# PCB_board.net
KiCad netlist of a schematic drawn in EAGLE
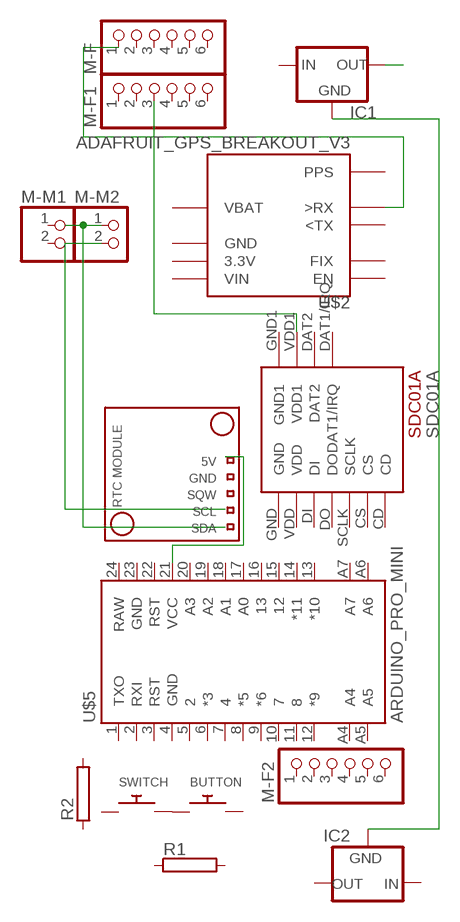
[diagram p0: schematic, sheet 1]

(export (version "E")
  (design (tool "Eeschema 10.0.6"))
  (components
    (comp (ref "BUTTON")
      (value "SWITCH_PUSHBUTTONSOFTTOUCHSMD_SJ")
      (footprint "eagle-import:PUSHBUTTON_SMD_SJ")
      (libsource (lib "eagle-import") (part "SWITCH_PUSHBUTTONSOFTTOUCHSMD_SJ"))
    )
    (comp (ref "IC1")
      (value "78XX/TO3")
      (footprint "eagle-import:TO3_78")
      (libsource (lib "eagle-import") (part "78XX/TO3"))
    )
    (comp (ref "IC2")
      (value "78XX/TO3")
      (footprint "eagle-import:TO3_78")
      (libsource (lib "eagle-import") (part "78XX/TO3"))
    )
    (comp (ref "M-F")
      (value "PINHD-1X6")
      (footprint "eagle-import:1X06")
      (libsource (lib "eagle-import") (part "PINHD-1X6"))
    )
    (comp (ref "M-F1")
      (value "PINHD-1X6")
      (footprint "eagle-import:1X06")
      (libsource (lib "eagle-import") (part "PINHD-1X6"))
    )
    (comp (ref "M-F2")
      (value "PINHD-1X6")
      (footprint "eagle-import:1X06")
      (libsource (lib "eagle-import") (part "PINHD-1X6"))
    )
    (comp (ref "M-M1")
      (value "PINHD-1X2")
      (footprint "eagle-import:1X02")
      (libsource (lib "eagle-import") (part "PINHD-1X2"))
    )
    (comp (ref "M-M2")
      (value "PINHD-1X2")
      (footprint "eagle-import:1X02")
      (libsource (lib "eagle-import") (part "PINHD-1X2"))
    )
    (comp (ref "R1")
      (value "RMG100-V")
      (footprint "eagle-import:TO-247-2V")
      (libsource (lib "eagle-import") (part "RMG100-V"))
    )
    (comp (ref "R2")
      (value "RMG100-V")
      (footprint "eagle-import:TO-247-2V")
      (libsource (lib "eagle-import") (part "RMG100-V"))
    )
    (comp (ref "SWITCH")
      (value "SWITCH_PUSHBUTTONEVQ-PE")
      (footprint "eagle-import:TACT_PANA-EVQ")
      (libsource (lib "eagle-import") (part "SWITCH_PUSHBUTTONEVQ-PE"))
    )
    (comp (ref "U$1")
      (value "REAL_TIME_CLOCK")
      (footprint "eagle-import:REAL_TIME_CLOCK")
      (libsource (lib "eagle-import") (part "REAL_TIME_CLOCK"))
    )
    (comp (ref "U$2")
      (value "ADAFRUIT_GPS_BREAKOUT_V3")
      (footprint "eagle-import:ADAFRUIT_GPS_BREAKOUT_V3")
      (libsource (lib "eagle-import") (part "ADAFRUIT_GPS_BREAKOUT_V3"))
    )
    (comp (ref "U$3")
      (value "SDC01A")
      (footprint "eagle-import:SDC01A")
      (libsource (lib "eagle-import") (part "SDC01A"))
    )
    (comp (ref "U$5")
      (value "ARDUINO_PRO_MINI")
      (footprint "eagle-import:ARDUINO_PRO_MINI")
      (libsource (lib "eagle-import") (part "ARDUINO_PRO_MINI"))
    )
  )
  (nets
    (net (code "1") (name "/3.3V") (class "Default")
      (node (ref "U$2") (pin "3.3V") (pinfunction "3.3V_3.3V") (pintype "power_in"))
    )
    (net (code "2") (name "/GND") (class "Default")
      (node (ref "U$2") (pin "GND") (pinfunction "GND_GND") (pintype "power_in"))
    )
    (net (code "3") (name "/VBAT") (class "Default")
      (node (ref "U$2") (pin "VBAT") (pinfunction "VBAT_VBAT") (pintype "power_in"))
    )
    (net (code "4") (name "/VIN") (class "Default")
      (node (ref "U$2") (pin "VIN") (pinfunction "VIN_VIN") (pintype "power_in"))
    )
    (net (code "5") (name "Net-(BUTTON-PadP$1)") (class "Default")
      (node (ref "BUTTON") (pin "P$1") (pinfunction "P$1_P$1") (pintype "passive"))
      (node (ref "SWITCH") (pin "P$2") (pinfunction "P$2_P$2") (pintype "passive"))
    )
    (net (code "6") (name "Net-(IC1-GND)") (class "Default")
      (node (ref "IC1") (pin "3") (pinfunction "GND_3") (pintype "input"))
      (node (ref "IC2") (pin "3") (pinfunction "GND_3") (pintype "input"))
    )
    (net (code "7") (name "Net-(M-F1-Pad3)") (class "Default")
      (node (ref "M-F1") (pin "3") (pinfunction "3_3") (pintype "passive"))
      (node (ref "U$3") (pin "VDD1") (pinfunction "VDD1_VDD1") (pintype "bidirectional"))
    )
    (net (code "8") (name "Net-(U$2->RX)") (class "Default")
      (node (ref "M-F") (pin "1") (pinfunction "1_1") (pintype "passive"))
      (node (ref "U$2") (pin "RX") (pinfunction ">RX_RX") (pintype "input"))
    )
    (net (code "9") (name "unconnected-(BUTTON-PadP$2)") (class "Default")
      (node (ref "BUTTON") (pin "P$2") (pinfunction "P$2_P$2") (pintype "passive"))
    )
    (net (code "10") (name "unconnected-(IC1-IN-Pad2)") (class "Default")
      (node (ref "IC1") (pin "2") (pinfunction "IN_2") (pintype "input"))
    )
    (net (code "11") (name "unconnected-(IC1-OUT-Pad1)") (class "Default")
      (node (ref "IC1") (pin "1") (pinfunction "OUT_1") (pintype "passive"))
    )
    (net (code "12") (name "unconnected-(IC2-IN-Pad2)") (class "Default")
      (node (ref "IC2") (pin "2") (pinfunction "IN_2") (pintype "input"))
    )
    (net (code "13") (name "unconnected-(IC2-OUT-Pad1)") (class "Default")
      (node (ref "IC2") (pin "1") (pinfunction "OUT_1") (pintype "passive"))
    )
    (net (code "14") (name "unconnected-(M-F-Pad2)") (class "Default")
      (node (ref "M-F") (pin "2") (pinfunction "2_2") (pintype "passive"))
    )
    (net (code "15") (name "unconnected-(M-F-Pad3)") (class "Default")
      (node (ref "M-F") (pin "3") (pinfunction "3_3") (pintype "passive"))
    )
    (net (code "16") (name "unconnected-(M-F-Pad4)") (class "Default")
      (node (ref "M-F") (pin "4") (pinfunction "4_4") (pintype "passive"))
    )
    (net (code "17") (name "unconnected-(M-F-Pad5)") (class "Default")
      (node (ref "M-F") (pin "5") (pinfunction "5_5") (pintype "passive"))
    )
    (net (code "18") (name "unconnected-(M-F-Pad6)") (class "Default")
      (node (ref "M-F") (pin "6") (pinfunction "6_6") (pintype "passive"))
    )
    (net (code "19") (name "unconnected-(M-F1-Pad1)") (class "Default")
      (node (ref "M-F1") (pin "1") (pinfunction "1_1") (pintype "passive"))
    )
    (net (code "20") (name "unconnected-(M-F1-Pad2)") (class "Default")
      (node (ref "M-F1") (pin "2") (pinfunction "2_2") (pintype "passive"))
    )
    (net (code "21") (name "unconnected-(M-F1-Pad4)") (class "Default")
      (node (ref "M-F1") (pin "4") (pinfunction "4_4") (pintype "passive"))
    )
    (net (code "22") (name "unconnected-(M-F1-Pad5)") (class "Default")
      (node (ref "M-F1") (pin "5") (pinfunction "5_5") (pintype "passive"))
    )
    (net (code "23") (name "unconnected-(M-F1-Pad6)") (class "Default")
      (node (ref "M-F1") (pin "6") (pinfunction "6_6") (pintype "passive"))
    )
    (net (code "24") (name "unconnected-(M-F2-Pad1)") (class "Default")
      (node (ref "M-F2") (pin "1") (pinfunction "1_1") (pintype "passive"))
    )
    (net (code "25") (name "unconnected-(M-F2-Pad2)") (class "Default")
      (node (ref "M-F2") (pin "2") (pinfunction "2_2") (pintype "passive"))
    )
    (net (code "26") (name "unconnected-(M-F2-Pad3)") (class "Default")
      (node (ref "M-F2") (pin "3") (pinfunction "3_3") (pintype "passive"))
    )
    (net (code "27") (name "unconnected-(M-F2-Pad4)") (class "Default")
      (node (ref "M-F2") (pin "4") (pinfunction "4_4") (pintype "passive"))
    )
    (net (code "28") (name "unconnected-(M-F2-Pad5)") (class "Default")
      (node (ref "M-F2") (pin "5") (pinfunction "5_5") (pintype "passive"))
    )
    (net (code "29") (name "unconnected-(M-F2-Pad6)") (class "Default")
      (node (ref "M-F2") (pin "6") (pinfunction "6_6") (pintype "passive"))
    )
    (net (code "30") (name "unconnected-(M-M1-Pad1)") (class "Default")
      (node (ref "M-M1") (pin "1") (pinfunction "1_1") (pintype "passive"))
    )
    (net (code "31") (name "unconnected-(M-M1-Pad2)") (class "Default")
      (node (ref "M-M1") (pin "2") (pinfunction "2_2") (pintype "passive"))
    )
    (net (code "32") (name "unconnected-(M-M2-Pad1)") (class "Default")
      (node (ref "M-M2") (pin "1") (pinfunction "1_1") (pintype "passive"))
    )
    (net (code "33") (name "unconnected-(M-M2-Pad2)") (class "Default")
      (node (ref "M-M2") (pin "2") (pinfunction "2_2") (pintype "passive"))
    )
    (net (code "34") (name "unconnected-(R1-Pad1)") (class "Default")
      (node (ref "R1") (pin "1") (pinfunction "1_1") (pintype "passive"))
    )
    (net (code "35") (name "unconnected-(R1-Pad2)") (class "Default")
      (node (ref "R1") (pin "2") (pinfunction "2_2") (pintype "passive"))
    )
    (net (code "36") (name "unconnected-(R2-Pad1)") (class "Default")
      (node (ref "R2") (pin "1") (pinfunction "1_1") (pintype "passive"))
    )
    (net (code "37") (name "unconnected-(R2-Pad2)") (class "Default")
      (node (ref "R2") (pin "2") (pinfunction "2_2") (pintype "passive"))
    )
    (net (code "38") (name "unconnected-(SWITCH-PadP$1)") (class "Default")
      (node (ref "SWITCH") (pin "P$1") (pinfunction "P$1_P$1") (pintype "passive"))
    )
    (net (code "39") (name "unconnected-(U$2-<TX-PadTX)") (class "Default")
      (node (ref "U$2") (pin "TX") (pinfunction "<TX_TX") (pintype "output"))
    )
    (net (code "40") (name "unconnected-(U$2-PadEN)") (class "Default")
      (node (ref "U$2") (pin "EN") (pinfunction "EN_EN") (pintype "bidirectional"))
    )
    (net (code "41") (name "unconnected-(U$2-PadFIX)") (class "Default")
      (node (ref "U$2") (pin "FIX") (pinfunction "FIX_FIX") (pintype "bidirectional"))
    )
    (net (code "42") (name "unconnected-(U$2-PadPPS)") (class "Default")
      (node (ref "U$2") (pin "PPS") (pinfunction "PPS_PPS") (pintype "bidirectional"))
    )
    (net (code "43") (name "unconnected-(U$3-PadCD)") (class "Default")
      (node (ref "U$3") (pin "CD") (pinfunction "CD_CD") (pintype "bidirectional"))
    )
    (net (code "44") (name "unconnected-(U$3-PadCS)") (class "Default")
      (node (ref "U$3") (pin "CS") (pinfunction "CS_CS") (pintype "bidirectional"))
    )
    (net (code "45") (name "unconnected-(U$3-PadDAT1{slash}IRQ)") (class "Default")
      (node (ref "U$3") (pin "DAT1/IRQ") (pinfunction "DAT1/IRQ_DAT1/IRQ") (pintype "bidirectional"))
    )
    (net (code "46") (name "unconnected-(U$3-PadDAT2)") (class "Default")
      (node (ref "U$3") (pin "DAT2") (pinfunction "DAT2_DAT2") (pintype "bidirectional"))
    )
    (net (code "47") (name "unconnected-(U$3-PadDI)") (class "Default")
      (node (ref "U$3") (pin "DI") (pinfunction "DI_DI") (pintype "bidirectional"))
    )
    (net (code "48") (name "unconnected-(U$3-PadDO)") (class "Default")
      (node (ref "U$3") (pin "DO") (pinfunction "DO_DO") (pintype "bidirectional"))
    )
    (net (code "49") (name "unconnected-(U$3-PadGND)") (class "Default")
      (node (ref "U$3") (pin "GND") (pinfunction "GND_GND") (pintype "bidirectional"))
    )
    (net (code "50") (name "unconnected-(U$3-PadGND1)") (class "Default")
      (node (ref "U$3") (pin "GND1") (pinfunction "GND1_GND1") (pintype "bidirectional"))
    )
    (net (code "51") (name "unconnected-(U$3-PadSCLK)") (class "Default")
      (node (ref "U$3") (pin "SCLK") (pinfunction "SCLK_SCLK") (pintype "bidirectional"))
    )
    (net (code "52") (name "unconnected-(U$3-PadVDD)") (class "Default")
      (node (ref "U$3") (pin "VDD") (pinfunction "VDD_VDD") (pintype "bidirectional"))
    )
    (net (code "53") (name "unconnected-(U$5-*3-Pad6)") (class "Default")
      (node (ref "U$5") (pin "6") (pinfunction "*3_6") (pintype "bidirectional"))
    )
    (net (code "54") (name "unconnected-(U$5-*5-Pad8)") (class "Default")
      (node (ref "U$5") (pin "8") (pinfunction "*5_8") (pintype "bidirectional"))
    )
    (net (code "55") (name "unconnected-(U$5-*6-Pad9)") (class "Default")
      (node (ref "U$5") (pin "9") (pinfunction "*6_9") (pintype "bidirectional"))
    )
    (net (code "56") (name "unconnected-(U$5-*9-Pad12)") (class "Default")
      (node (ref "U$5") (pin "12") (pinfunction "*9_12") (pintype "bidirectional"))
    )
    (net (code "57") (name "unconnected-(U$5-*10-Pad13)") (class "Default")
      (node (ref "U$5") (pin "13") (pinfunction "*10_13") (pintype "bidirectional"))
    )
    (net (code "58") (name "unconnected-(U$5-*11-Pad14)") (class "Default")
      (node (ref "U$5") (pin "14") (pinfunction "*11_14") (pintype "bidirectional"))
    )
    (net (code "59") (name "unconnected-(U$5-2-Pad5)") (class "Default")
      (node (ref "U$5") (pin "5") (pinfunction "2_5") (pintype "bidirectional"))
    )
    (net (code "60") (name "unconnected-(U$5-4-Pad7)") (class "Default")
      (node (ref "U$5") (pin "7") (pinfunction "4_7") (pintype "bidirectional"))
    )
    (net (code "61") (name "unconnected-(U$5-7-Pad10)") (class "Default")
      (node (ref "U$5") (pin "10") (pinfunction "7_10") (pintype "bidirectional"))
    )
    (net (code "62") (name "unconnected-(U$5-8-Pad11)") (class "Default")
      (node (ref "U$5") (pin "11") (pinfunction "8_11") (pintype "bidirectional"))
    )
    (net (code "63") (name "unconnected-(U$5-12-Pad15)") (class "Default")
      (node (ref "U$5") (pin "15") (pinfunction "12_15") (pintype "bidirectional"))
    )
    (net (code "64") (name "unconnected-(U$5-13-Pad16)") (class "Default")
      (node (ref "U$5") (pin "16") (pinfunction "13_16") (pintype "bidirectional"))
    )
    (net (code "65") (name "unconnected-(U$5-A0-Pad17)") (class "Default")
      (node (ref "U$5") (pin "17") (pinfunction "A0_17") (pintype "bidirectional"))
    )
    (net (code "66") (name "unconnected-(U$5-A1-Pad18)") (class "Default")
      (node (ref "U$5") (pin "18") (pinfunction "A1_18") (pintype "bidirectional"))
    )
    (net (code "67") (name "unconnected-(U$5-A2-Pad19)") (class "Default")
      (node (ref "U$5") (pin "19") (pinfunction "A2_19") (pintype "bidirectional"))
    )
    (net (code "68") (name "unconnected-(U$5-A3-Pad20)") (class "Default")
      (node (ref "U$5") (pin "20") (pinfunction "A3_20") (pintype "bidirectional"))
    )
    (net (code "69") (name "unconnected-(U$5-GND-Pad4)") (class "Default")
      (node (ref "U$5") (pin "4") (pinfunction "GND_4") (pintype "bidirectional"))
    )
    (net (code "70") (name "unconnected-(U$5-GND-Pad23)") (class "Default")
      (node (ref "U$5") (pin "23") (pinfunction "GND_23") (pintype "bidirectional"))
    )
    (net (code "71") (name "unconnected-(U$5-PadA4)") (class "Default")
      (node (ref "U$5") (pin "A4") (pinfunction "A4_A4") (pintype "bidirectional"))
    )
    (net (code "72") (name "unconnected-(U$5-PadA5)") (class "Default")
      (node (ref "U$5") (pin "A5") (pinfunction "A5_A5") (pintype "bidirectional"))
    )
    (net (code "73") (name "unconnected-(U$5-PadA6)") (class "Default")
      (node (ref "U$5") (pin "A6") (pinfunction "A6_A6") (pintype "bidirectional"))
    )
    (net (code "74") (name "unconnected-(U$5-PadA7)") (class "Default")
      (node (ref "U$5") (pin "A7") (pinfunction "A7_A7") (pintype "bidirectional"))
    )
    (net (code "75") (name "unconnected-(U$5-RAW-Pad24)") (class "Default")
      (node (ref "U$5") (pin "24") (pinfunction "RAW_24") (pintype "bidirectional"))
    )
    (net (code "76") (name "unconnected-(U$5-RST-Pad3)") (class "Default")
      (node (ref "U$5") (pin "3") (pinfunction "RST_3") (pintype "bidirectional"))
    )
    (net (code "77") (name "unconnected-(U$5-RST-Pad22)") (class "Default")
      (node (ref "U$5") (pin "22") (pinfunction "RST_22") (pintype "bidirectional"))
    )
    (net (code "78") (name "unconnected-(U$5-RXI-Pad2)") (class "Default")
      (node (ref "U$5") (pin "2") (pinfunction "RXI_2") (pintype "bidirectional"))
    )
    (net (code "79") (name "unconnected-(U$5-TXO-Pad1)") (class "Default")
      (node (ref "U$5") (pin "1") (pinfunction "TXO_1") (pintype "bidirectional"))
    )
    (net (code "80") (name "unconnected-(U$5-VCC-Pad21)") (class "Default")
      (node (ref "U$5") (pin "21") (pinfunction "VCC_21") (pintype "bidirectional"))
    )
  )
)
